# design.net
KiCad netlist of a schematic drawn in EAGLE
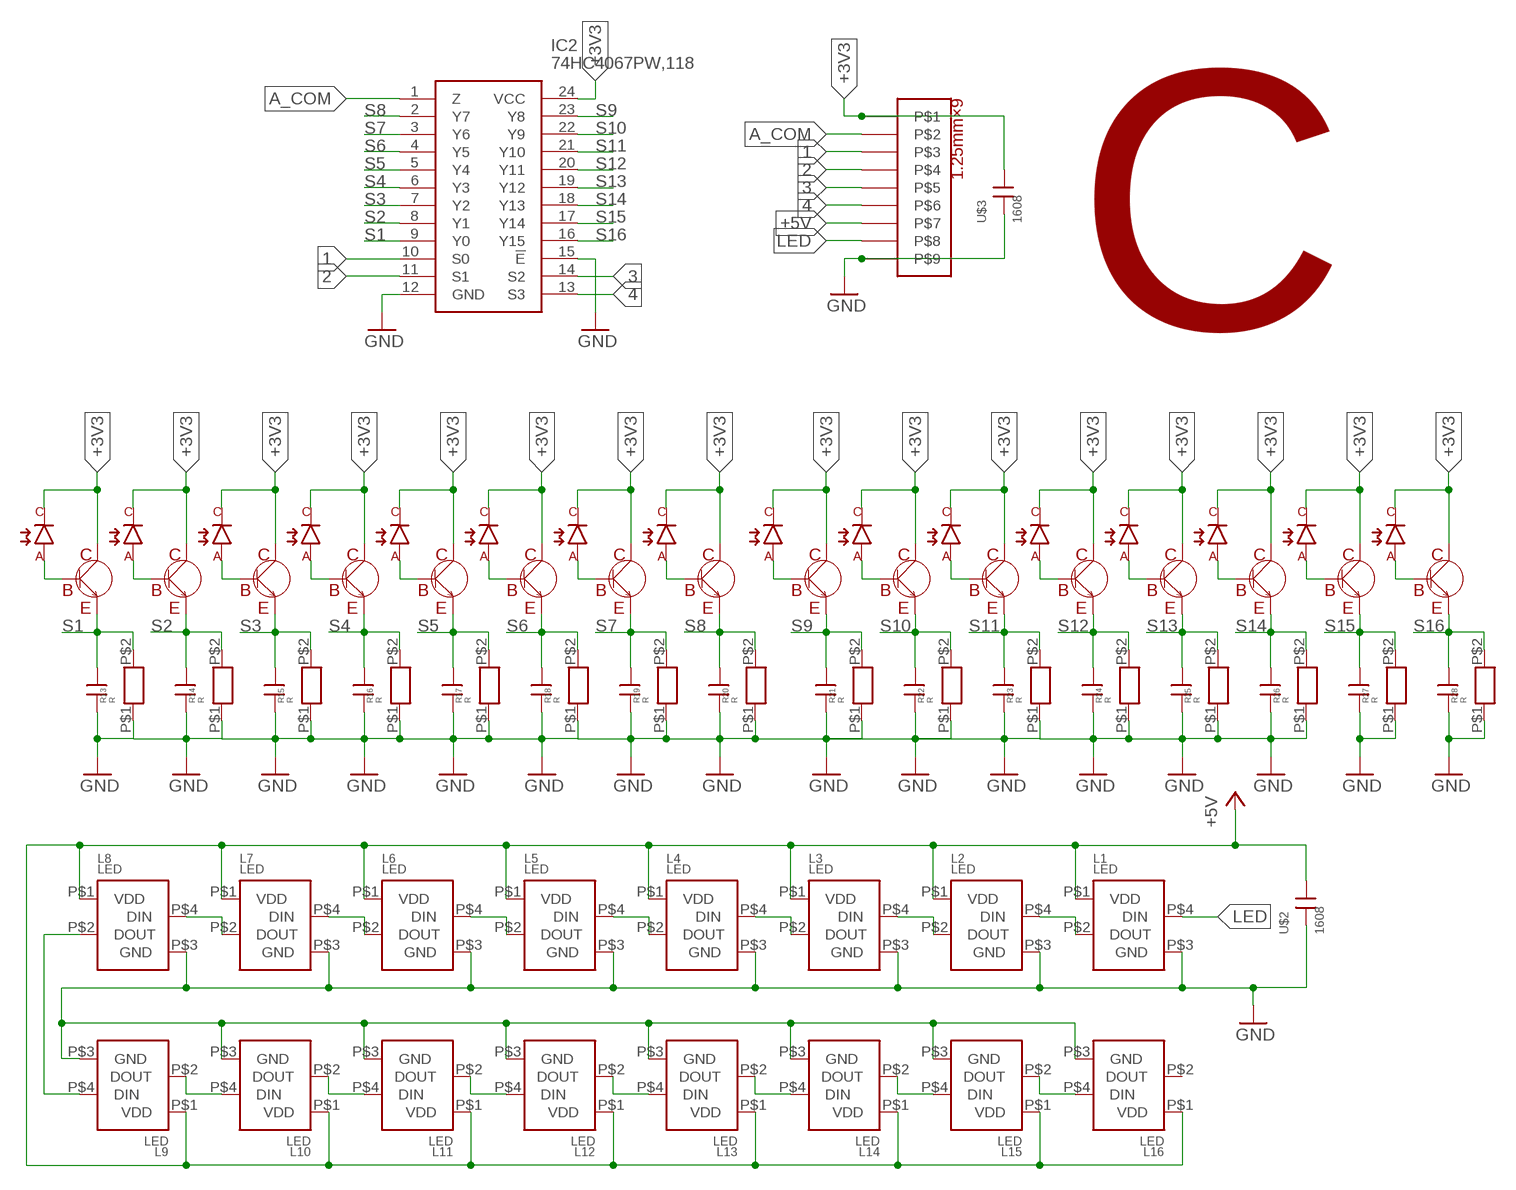
[diagram p0: schematic, sheet 1]

(export (version "E")
  (design (tool "Eeschema 10.0.6"))
  (components
    (comp (ref "C13")
      (value "1608")
      (footprint "eagle-import:CON")
      (libsource (lib "eagle-import") (part "1608"))
    )
    (comp (ref "C14")
      (value "1608")
      (footprint "eagle-import:CON")
      (libsource (lib "eagle-import") (part "1608"))
    )
    (comp (ref "C15")
      (value "1608")
      (footprint "eagle-import:CON")
      (libsource (lib "eagle-import") (part "1608"))
    )
    (comp (ref "C16")
      (value "1608")
      (footprint "eagle-import:CON")
      (libsource (lib "eagle-import") (part "1608"))
    )
    (comp (ref "C17")
      (value "1608")
      (footprint "eagle-import:CON")
      (libsource (lib "eagle-import") (part "1608"))
    )
    (comp (ref "C18")
      (value "1608")
      (footprint "eagle-import:CON")
      (libsource (lib "eagle-import") (part "1608"))
    )
    (comp (ref "C19")
      (value "1608")
      (footprint "eagle-import:CON")
      (libsource (lib "eagle-import") (part "1608"))
    )
    (comp (ref "C20")
      (value "1608")
      (footprint "eagle-import:CON")
      (libsource (lib "eagle-import") (part "1608"))
    )
    (comp (ref "C21")
      (value "1608")
      (footprint "eagle-import:CON")
      (libsource (lib "eagle-import") (part "1608"))
    )
    (comp (ref "C22")
      (value "1608")
      (footprint "eagle-import:CON")
      (libsource (lib "eagle-import") (part "1608"))
    )
    (comp (ref "C23")
      (value "1608")
      (footprint "eagle-import:CON")
      (libsource (lib "eagle-import") (part "1608"))
    )
    (comp (ref "C24")
      (value "1608")
      (footprint "eagle-import:CON")
      (libsource (lib "eagle-import") (part "1608"))
    )
    (comp (ref "C25")
      (value "1608")
      (footprint "eagle-import:CON")
      (libsource (lib "eagle-import") (part "1608"))
    )
    (comp (ref "C26")
      (value "1608")
      (footprint "eagle-import:CON")
      (libsource (lib "eagle-import") (part "1608"))
    )
    (comp (ref "C27")
      (value "1608")
      (footprint "eagle-import:CON")
      (libsource (lib "eagle-import") (part "1608"))
    )
    (comp (ref "C28")
      (value "1608")
      (footprint "eagle-import:CON")
      (libsource (lib "eagle-import") (part "1608"))
    )
    (comp (ref "IC2")
      (value "74HC4067PW,118")
      (footprint "eagle-import:SOP65P640X110-24N")
      (fields (field (name "MOUSER_PART_NUMBER") "771-74HC4067PW-T"))
      (libsource (lib "eagle-import") (part "74HC4067PW,118"))
    )
    (comp (ref "L1")
      (value "LED")
      (footprint "eagle-import:LED")
      (libsource (lib "eagle-import") (part "LED"))
    )
    (comp (ref "L2")
      (value "LED")
      (footprint "eagle-import:LED")
      (libsource (lib "eagle-import") (part "LED"))
    )
    (comp (ref "L3")
      (value "LED")
      (footprint "eagle-import:LED")
      (libsource (lib "eagle-import") (part "LED"))
    )
    (comp (ref "L4")
      (value "LED")
      (footprint "eagle-import:LED")
      (libsource (lib "eagle-import") (part "LED"))
    )
    (comp (ref "L5")
      (value "LED")
      (footprint "eagle-import:LED")
      (libsource (lib "eagle-import") (part "LED"))
    )
    (comp (ref "L6")
      (value "LED")
      (footprint "eagle-import:LED")
      (libsource (lib "eagle-import") (part "LED"))
    )
    (comp (ref "L7")
      (value "LED")
      (footprint "eagle-import:LED")
      (libsource (lib "eagle-import") (part "LED"))
    )
    (comp (ref "L8")
      (value "LED")
      (footprint "eagle-import:LED")
      (libsource (lib "eagle-import") (part "LED"))
    )
    (comp (ref "L9")
      (value "LED")
      (footprint "eagle-import:LED")
      (libsource (lib "eagle-import") (part "LED"))
    )
    (comp (ref "L10")
      (value "LED")
      (footprint "eagle-import:LED")
      (libsource (lib "eagle-import") (part "LED"))
    )
    (comp (ref "L11")
      (value "LED")
      (footprint "eagle-import:LED")
      (libsource (lib "eagle-import") (part "LED"))
    )
    (comp (ref "L12")
      (value "LED")
      (footprint "eagle-import:LED")
      (libsource (lib "eagle-import") (part "LED"))
    )
    (comp (ref "L13")
      (value "LED")
      (footprint "eagle-import:LED")
      (libsource (lib "eagle-import") (part "LED"))
    )
    (comp (ref "L14")
      (value "LED")
      (footprint "eagle-import:LED")
      (libsource (lib "eagle-import") (part "LED"))
    )
    (comp (ref "L15")
      (value "LED")
      (footprint "eagle-import:LED")
      (libsource (lib "eagle-import") (part "LED"))
    )
    (comp (ref "L16")
      (value "LED")
      (footprint "eagle-import:LED")
      (libsource (lib "eagle-import") (part "LED"))
    )
    (comp (ref "P1")
      (value "フォトダイオード")
      (footprint "eagle-import:フォトダイオード")
      (libsource (lib "eagle-import") (part "フォトダイオード"))
    )
    (comp (ref "P2")
      (value "フォトダイオード")
      (footprint "eagle-import:フォトダイオード")
      (libsource (lib "eagle-import") (part "フォトダイオード"))
    )
    (comp (ref "P3")
      (value "フォトダイオード")
      (footprint "eagle-import:フォトダイオード")
      (libsource (lib "eagle-import") (part "フォトダイオード"))
    )
    (comp (ref "P4")
      (value "フォトダイオード")
      (footprint "eagle-import:フォトダイオード")
      (libsource (lib "eagle-import") (part "フォトダイオード"))
    )
    (comp (ref "P5")
      (value "フォトダイオード")
      (footprint "eagle-import:フォトダイオード")
      (libsource (lib "eagle-import") (part "フォトダイオード"))
    )
    (comp (ref "P6")
      (value "フォトダイオード")
      (footprint "eagle-import:フォトダイオード")
      (libsource (lib "eagle-import") (part "フォトダイオード"))
    )
    (comp (ref "P7")
      (value "フォトダイオード")
      (footprint "eagle-import:フォトダイオード")
      (libsource (lib "eagle-import") (part "フォトダイオード"))
    )
    (comp (ref "P8")
      (value "フォトダイオード")
      (footprint "eagle-import:フォトダイオード")
      (libsource (lib "eagle-import") (part "フォトダイオード"))
    )
    (comp (ref "P9")
      (value "フォトダイオード")
      (footprint "eagle-import:フォトダイオード")
      (libsource (lib "eagle-import") (part "フォトダイオード"))
    )
    (comp (ref "P10")
      (value "フォトダイオード")
      (footprint "eagle-import:フォトダイオード")
      (libsource (lib "eagle-import") (part "フォトダイオード"))
    )
    (comp (ref "P11")
      (value "フォトダイオード")
      (footprint "eagle-import:フォトダイオード")
      (libsource (lib "eagle-import") (part "フォトダイオード"))
    )
    (comp (ref "P12")
      (value "フォトダイオード")
      (footprint "eagle-import:フォトダイオード")
      (libsource (lib "eagle-import") (part "フォトダイオード"))
    )
    (comp (ref "P13")
      (value "フォトダイオード")
      (footprint "eagle-import:フォトダイオード")
      (libsource (lib "eagle-import") (part "フォトダイオード"))
    )
    (comp (ref "P14")
      (value "フォトダイオード")
      (footprint "eagle-import:フォトダイオード")
      (libsource (lib "eagle-import") (part "フォトダイオード"))
    )
    (comp (ref "P15")
      (value "フォトダイオード")
      (footprint "eagle-import:フォトダイオード")
      (libsource (lib "eagle-import") (part "フォトダイオード"))
    )
    (comp (ref "P16")
      (value "フォトダイオード")
      (footprint "eagle-import:フォトダイオード")
      (libsource (lib "eagle-import") (part "フォトダイオード"))
    )
    (comp (ref "R13") (value "R") (footprint "eagle-import:1608") (libsource (lib "eagle-import") (part "R")))
    (comp (ref "R14") (value "R") (footprint "eagle-import:1608") (libsource (lib "eagle-import") (part "R")))
    (comp (ref "R15") (value "R") (footprint "eagle-import:1608") (libsource (lib "eagle-import") (part "R")))
    (comp (ref "R16") (value "R") (footprint "eagle-import:1608") (libsource (lib "eagle-import") (part "R")))
    (comp (ref "R17") (value "R") (footprint "eagle-import:1608") (libsource (lib "eagle-import") (part "R")))
    (comp (ref "R18") (value "R") (footprint "eagle-import:1608") (libsource (lib "eagle-import") (part "R")))
    (comp (ref "R19") (value "R") (footprint "eagle-import:1608") (libsource (lib "eagle-import") (part "R")))
    (comp (ref "R20") (value "R") (footprint "eagle-import:1608") (libsource (lib "eagle-import") (part "R")))
    (comp (ref "R21") (value "R") (footprint "eagle-import:1608") (libsource (lib "eagle-import") (part "R")))
    (comp (ref "R22") (value "R") (footprint "eagle-import:1608") (libsource (lib "eagle-import") (part "R")))
    (comp (ref "R23") (value "R") (footprint "eagle-import:1608") (libsource (lib "eagle-import") (part "R")))
    (comp (ref "R24") (value "R") (footprint "eagle-import:1608") (libsource (lib "eagle-import") (part "R")))
    (comp (ref "R25") (value "R") (footprint "eagle-import:1608") (libsource (lib "eagle-import") (part "R")))
    (comp (ref "R26") (value "R") (footprint "eagle-import:1608") (libsource (lib "eagle-import") (part "R")))
    (comp (ref "R27") (value "R") (footprint "eagle-import:1608") (libsource (lib "eagle-import") (part "R")))
    (comp (ref "R28") (value "R") (footprint "eagle-import:1608") (libsource (lib "eagle-import") (part "R")))
    (comp (ref "T1")
      (value "2CS2712")
      (footprint "eagle-import:TRANS_SSM3J325F,LF")
      (libsource (lib "eagle-import") (part "2CS2712"))
    )
    (comp (ref "T2")
      (value "2CS2712")
      (footprint "eagle-import:TRANS_SSM3J325F,LF")
      (libsource (lib "eagle-import") (part "2CS2712"))
    )
    (comp (ref "T3")
      (value "2CS2712")
      (footprint "eagle-import:TRANS_SSM3J325F,LF")
      (libsource (lib "eagle-import") (part "2CS2712"))
    )
    (comp (ref "T4")
      (value "2CS2712")
      (footprint "eagle-import:TRANS_SSM3J325F,LF")
      (libsource (lib "eagle-import") (part "2CS2712"))
    )
    (comp (ref "T5")
      (value "2CS2712")
      (footprint "eagle-import:TRANS_SSM3J325F,LF")
      (libsource (lib "eagle-import") (part "2CS2712"))
    )
    (comp (ref "T6")
      (value "2CS2712")
      (footprint "eagle-import:TRANS_SSM3J325F,LF")
      (libsource (lib "eagle-import") (part "2CS2712"))
    )
    (comp (ref "T7")
      (value "2CS2712")
      (footprint "eagle-import:TRANS_SSM3J325F,LF")
      (libsource (lib "eagle-import") (part "2CS2712"))
    )
    (comp (ref "T8")
      (value "2CS2712")
      (footprint "eagle-import:TRANS_SSM3J325F,LF")
      (libsource (lib "eagle-import") (part "2CS2712"))
    )
    (comp (ref "T9")
      (value "2CS2712")
      (footprint "eagle-import:TRANS_SSM3J325F,LF")
      (libsource (lib "eagle-import") (part "2CS2712"))
    )
    (comp (ref "T10")
      (value "2CS2712")
      (footprint "eagle-import:TRANS_SSM3J325F,LF")
      (libsource (lib "eagle-import") (part "2CS2712"))
    )
    (comp (ref "T11")
      (value "2CS2712")
      (footprint "eagle-import:TRANS_SSM3J325F,LF")
      (libsource (lib "eagle-import") (part "2CS2712"))
    )
    (comp (ref "T12")
      (value "2CS2712")
      (footprint "eagle-import:TRANS_SSM3J325F,LF")
      (libsource (lib "eagle-import") (part "2CS2712"))
    )
    (comp (ref "T13")
      (value "2CS2712")
      (footprint "eagle-import:TRANS_SSM3J325F,LF")
      (libsource (lib "eagle-import") (part "2CS2712"))
    )
    (comp (ref "T14")
      (value "2CS2712")
      (footprint "eagle-import:TRANS_SSM3J325F,LF")
      (libsource (lib "eagle-import") (part "2CS2712"))
    )
    (comp (ref "T15")
      (value "2CS2712")
      (footprint "eagle-import:TRANS_SSM3J325F,LF")
      (libsource (lib "eagle-import") (part "2CS2712"))
    )
    (comp (ref "T16")
      (value "2CS2712")
      (footprint "eagle-import:TRANS_SSM3J325F,LF")
      (libsource (lib "eagle-import") (part "2CS2712"))
    )
    (comp (ref "U$1")
      (value "1MMCON")
      (footprint "eagle-import:1MMCON")
      (libsource (lib "eagle-import") (part "1MMCON"))
    )
    (comp (ref "U$2")
      (value "1608")
      (footprint "eagle-import:CON")
      (libsource (lib "eagle-import") (part "1608"))
    )
    (comp (ref "U$3")
      (value "1608")
      (footprint "eagle-import:CON")
      (libsource (lib "eagle-import") (part "1608"))
    )
  )
  (nets
    (net (code "1") (name "+3V3") (class "Default")
      (node (ref "IC2") (pin "24") (pinfunction "VCC_24") (pintype "bidirectional"))
      (node (ref "P1") (pin "C") (pinfunction "C_C") (pintype "bidirectional"))
      (node (ref "P10") (pin "C") (pinfunction "C_C") (pintype "bidirectional"))
      (node (ref "P11") (pin "C") (pinfunction "C_C") (pintype "bidirectional"))
      (node (ref "P12") (pin "C") (pinfunction "C_C") (pintype "bidirectional"))
      (node (ref "P13") (pin "C") (pinfunction "C_C") (pintype "bidirectional"))
      (node (ref "P14") (pin "C") (pinfunction "C_C") (pintype "bidirectional"))
      (node (ref "P15") (pin "C") (pinfunction "C_C") (pintype "bidirectional"))
      (node (ref "P16") (pin "C") (pinfunction "C_C") (pintype "bidirectional"))
      (node (ref "P2") (pin "C") (pinfunction "C_C") (pintype "bidirectional"))
      (node (ref "P3") (pin "C") (pinfunction "C_C") (pintype "bidirectional"))
      (node (ref "P4") (pin "C") (pinfunction "C_C") (pintype "bidirectional"))
      (node (ref "P5") (pin "C") (pinfunction "C_C") (pintype "bidirectional"))
      (node (ref "P6") (pin "C") (pinfunction "C_C") (pintype "bidirectional"))
      (node (ref "P7") (pin "C") (pinfunction "C_C") (pintype "bidirectional"))
      (node (ref "P8") (pin "C") (pinfunction "C_C") (pintype "bidirectional"))
      (node (ref "P9") (pin "C") (pinfunction "C_C") (pintype "bidirectional"))
      (node (ref "T1") (pin "C") (pinfunction "C_C") (pintype "bidirectional"))
      (node (ref "T10") (pin "C") (pinfunction "C_C") (pintype "bidirectional"))
      (node (ref "T11") (pin "C") (pinfunction "C_C") (pintype "bidirectional"))
      (node (ref "T12") (pin "C") (pinfunction "C_C") (pintype "bidirectional"))
      (node (ref "T13") (pin "C") (pinfunction "C_C") (pintype "bidirectional"))
      (node (ref "T14") (pin "C") (pinfunction "C_C") (pintype "bidirectional"))
      (node (ref "T15") (pin "C") (pinfunction "C_C") (pintype "bidirectional"))
      (node (ref "T16") (pin "C") (pinfunction "C_C") (pintype "bidirectional"))
      (node (ref "T2") (pin "C") (pinfunction "C_C") (pintype "bidirectional"))
      (node (ref "T3") (pin "C") (pinfunction "C_C") (pintype "bidirectional"))
      (node (ref "T4") (pin "C") (pinfunction "C_C") (pintype "bidirectional"))
      (node (ref "T5") (pin "C") (pinfunction "C_C") (pintype "bidirectional"))
      (node (ref "T6") (pin "C") (pinfunction "C_C") (pintype "bidirectional"))
      (node (ref "T7") (pin "C") (pinfunction "C_C") (pintype "bidirectional"))
      (node (ref "T8") (pin "C") (pinfunction "C_C") (pintype "bidirectional"))
      (node (ref "T9") (pin "C") (pinfunction "C_C") (pintype "bidirectional"))
      (node (ref "U$1") (pin "P$1") (pinfunction "P$1_P$1") (pintype "bidirectional"))
      (node (ref "U$3") (pin "P$1") (pinfunction "1_P$1") (pintype "bidirectional"))
    )
    (net (code "2") (name "+5V") (class "Default")
      (node (ref "L1") (pin "P$1") (pinfunction "VDD_P$1") (pintype "bidirectional"))
      (node (ref "L10") (pin "P$1") (pinfunction "VDD_P$1") (pintype "bidirectional"))
      (node (ref "L11") (pin "P$1") (pinfunction "VDD_P$1") (pintype "bidirectional"))
      (node (ref "L12") (pin "P$1") (pinfunction "VDD_P$1") (pintype "bidirectional"))
      (node (ref "L13") (pin "P$1") (pinfunction "VDD_P$1") (pintype "bidirectional"))
      (node (ref "L14") (pin "P$1") (pinfunction "VDD_P$1") (pintype "bidirectional"))
      (node (ref "L15") (pin "P$1") (pinfunction "VDD_P$1") (pintype "bidirectional"))
      (node (ref "L16") (pin "P$1") (pinfunction "VDD_P$1") (pintype "bidirectional"))
      (node (ref "L2") (pin "P$1") (pinfunction "VDD_P$1") (pintype "bidirectional"))
      (node (ref "L3") (pin "P$1") (pinfunction "VDD_P$1") (pintype "bidirectional"))
      (node (ref "L4") (pin "P$1") (pinfunction "VDD_P$1") (pintype "bidirectional"))
      (node (ref "L5") (pin "P$1") (pinfunction "VDD_P$1") (pintype "bidirectional"))
      (node (ref "L6") (pin "P$1") (pinfunction "VDD_P$1") (pintype "bidirectional"))
      (node (ref "L7") (pin "P$1") (pinfunction "VDD_P$1") (pintype "bidirectional"))
      (node (ref "L8") (pin "P$1") (pinfunction "VDD_P$1") (pintype "bidirectional"))
      (node (ref "L9") (pin "P$1") (pinfunction "VDD_P$1") (pintype "bidirectional"))
      (node (ref "U$1") (pin "P$7") (pinfunction "P$7_P$7") (pintype "bidirectional"))
      (node (ref "U$2") (pin "P$1") (pinfunction "1_P$1") (pintype "bidirectional"))
    )
    (net (code "3") (name "/S1") (class "Default")
      (node (ref "C13") (pin "P$1") (pinfunction "1_P$1") (pintype "bidirectional"))
      (node (ref "IC2") (pin "9") (pinfunction "Y0_9") (pintype "bidirectional"))
      (node (ref "R13") (pin "P$2") (pinfunction "P$2_P$2") (pintype "bidirectional"))
      (node (ref "T1") (pin "E") (pinfunction "E_E") (pintype "bidirectional"))
    )
    (net (code "4") (name "/S2") (class "Default")
      (node (ref "C14") (pin "P$1") (pinfunction "1_P$1") (pintype "bidirectional"))
      (node (ref "IC2") (pin "8") (pinfunction "Y1_8") (pintype "bidirectional"))
      (node (ref "R14") (pin "P$2") (pinfunction "P$2_P$2") (pintype "bidirectional"))
      (node (ref "T2") (pin "E") (pinfunction "E_E") (pintype "bidirectional"))
    )
    (net (code "5") (name "/S3") (class "Default")
      (node (ref "C15") (pin "P$1") (pinfunction "1_P$1") (pintype "bidirectional"))
      (node (ref "IC2") (pin "7") (pinfunction "Y2_7") (pintype "bidirectional"))
      (node (ref "R15") (pin "P$2") (pinfunction "P$2_P$2") (pintype "bidirectional"))
      (node (ref "T3") (pin "E") (pinfunction "E_E") (pintype "bidirectional"))
    )
    (net (code "6") (name "/S4") (class "Default")
      (node (ref "C16") (pin "P$1") (pinfunction "1_P$1") (pintype "bidirectional"))
      (node (ref "IC2") (pin "6") (pinfunction "Y3_6") (pintype "bidirectional"))
      (node (ref "R16") (pin "P$2") (pinfunction "P$2_P$2") (pintype "bidirectional"))
      (node (ref "T4") (pin "E") (pinfunction "E_E") (pintype "bidirectional"))
    )
    (net (code "7") (name "/S5") (class "Default")
      (node (ref "C17") (pin "P$1") (pinfunction "1_P$1") (pintype "bidirectional"))
      (node (ref "IC2") (pin "5") (pinfunction "Y4_5") (pintype "bidirectional"))
      (node (ref "R17") (pin "P$2") (pinfunction "P$2_P$2") (pintype "bidirectional"))
      (node (ref "T5") (pin "E") (pinfunction "E_E") (pintype "bidirectional"))
    )
    (net (code "8") (name "/S6") (class "Default")
      (node (ref "C18") (pin "P$1") (pinfunction "1_P$1") (pintype "bidirectional"))
      (node (ref "IC2") (pin "4") (pinfunction "Y5_4") (pintype "bidirectional"))
      (node (ref "R18") (pin "P$2") (pinfunction "P$2_P$2") (pintype "bidirectional"))
      (node (ref "T6") (pin "E") (pinfunction "E_E") (pintype "bidirectional"))
    )
    (net (code "9") (name "/S7") (class "Default")
      (node (ref "C19") (pin "P$1") (pinfunction "1_P$1") (pintype "bidirectional"))
      (node (ref "IC2") (pin "3") (pinfunction "Y6_3") (pintype "bidirectional"))
      (node (ref "R19") (pin "P$2") (pinfunction "P$2_P$2") (pintype "bidirectional"))
      (node (ref "T7") (pin "E") (pinfunction "E_E") (pintype "bidirectional"))
    )
    (net (code "10") (name "/S8") (class "Default")
      (node (ref "C20") (pin "P$1") (pinfunction "1_P$1") (pintype "bidirectional"))
      (node (ref "IC2") (pin "2") (pinfunction "Y7_2") (pintype "bidirectional"))
      (node (ref "R20") (pin "P$2") (pinfunction "P$2_P$2") (pintype "bidirectional"))
      (node (ref "T8") (pin "E") (pinfunction "E_E") (pintype "bidirectional"))
    )
    (net (code "11") (name "/S9") (class "Default")
      (node (ref "C21") (pin "P$1") (pinfunction "1_P$1") (pintype "bidirectional"))
      (node (ref "IC2") (pin "23") (pinfunction "Y8_23") (pintype "bidirectional"))
      (node (ref "R21") (pin "P$2") (pinfunction "P$2_P$2") (pintype "bidirectional"))
      (node (ref "T9") (pin "E") (pinfunction "E_E") (pintype "bidirectional"))
    )
    (net (code "12") (name "/S10") (class "Default")
      (node (ref "C22") (pin "P$1") (pinfunction "1_P$1") (pintype "bidirectional"))
      (node (ref "IC2") (pin "22") (pinfunction "Y9_22") (pintype "bidirectional"))
      (node (ref "R22") (pin "P$2") (pinfunction "P$2_P$2") (pintype "bidirectional"))
      (node (ref "T10") (pin "E") (pinfunction "E_E") (pintype "bidirectional"))
    )
    (net (code "13") (name "/S11") (class "Default")
      (node (ref "C23") (pin "P$1") (pinfunction "1_P$1") (pintype "bidirectional"))
      (node (ref "IC2") (pin "21") (pinfunction "Y10_21") (pintype "bidirectional"))
      (node (ref "R23") (pin "P$2") (pinfunction "P$2_P$2") (pintype "bidirectional"))
      (node (ref "T11") (pin "E") (pinfunction "E_E") (pintype "bidirectional"))
    )
    (net (code "14") (name "/S12") (class "Default")
      (node (ref "C24") (pin "P$1") (pinfunction "1_P$1") (pintype "bidirectional"))
      (node (ref "IC2") (pin "20") (pinfunction "Y11_20") (pintype "bidirectional"))
      (node (ref "R24") (pin "P$2") (pinfunction "P$2_P$2") (pintype "bidirectional"))
      (node (ref "T12") (pin "E") (pinfunction "E_E") (pintype "bidirectional"))
    )
    (net (code "15") (name "/S13") (class "Default")
      (node (ref "C25") (pin "P$1") (pinfunction "1_P$1") (pintype "bidirectional"))
      (node (ref "IC2") (pin "19") (pinfunction "Y12_19") (pintype "bidirectional"))
      (node (ref "R25") (pin "P$2") (pinfunction "P$2_P$2") (pintype "bidirectional"))
      (node (ref "T13") (pin "E") (pinfunction "E_E") (pintype "bidirectional"))
    )
    (net (code "16") (name "/S14") (class "Default")
      (node (ref "C26") (pin "P$1") (pinfunction "1_P$1") (pintype "bidirectional"))
      (node (ref "IC2") (pin "18") (pinfunction "Y13_18") (pintype "bidirectional"))
      (node (ref "R26") (pin "P$2") (pinfunction "P$2_P$2") (pintype "bidirectional"))
      (node (ref "T14") (pin "E") (pinfunction "E_E") (pintype "bidirectional"))
    )
    (net (code "17") (name "/S15") (class "Default")
      (node (ref "C27") (pin "P$1") (pinfunction "1_P$1") (pintype "bidirectional"))
      (node (ref "IC2") (pin "17") (pinfunction "Y14_17") (pintype "bidirectional"))
      (node (ref "R27") (pin "P$2") (pinfunction "P$2_P$2") (pintype "bidirectional"))
      (node (ref "T15") (pin "E") (pinfunction "E_E") (pintype "bidirectional"))
    )
    (net (code "18") (name "/S16") (class "Default")
      (node (ref "C28") (pin "P$1") (pinfunction "1_P$1") (pintype "bidirectional"))
      (node (ref "IC2") (pin "16") (pinfunction "Y15_16") (pintype "bidirectional"))
      (node (ref "R28") (pin "P$2") (pinfunction "P$2_P$2") (pintype "bidirectional"))
      (node (ref "T16") (pin "E") (pinfunction "E_E") (pintype "bidirectional"))
    )
    (net (code "19") (name "1") (class "Default")
      (node (ref "IC2") (pin "10") (pinfunction "S0_10") (pintype "bidirectional"))
      (node (ref "U$1") (pin "P$3") (pinfunction "P$3_P$3") (pintype "bidirectional"))
    )
    (net (code "20") (name "2") (class "Default")
      (node (ref "IC2") (pin "11") (pinfunction "S1_11") (pintype "bidirectional"))
      (node (ref "U$1") (pin "P$4") (pinfunction "P$4_P$4") (pintype "bidirectional"))
    )
    (net (code "21") (name "3") (class "Default")
      (node (ref "IC2") (pin "14") (pinfunction "S2_14") (pintype "bidirectional"))
      (node (ref "U$1") (pin "P$5") (pinfunction "P$5_P$5") (pintype "bidirectional"))
    )
    (net (code "22") (name "4") (class "Default")
      (node (ref "IC2") (pin "13") (pinfunction "S3_13") (pintype "bidirectional"))
      (node (ref "U$1") (pin "P$6") (pinfunction "P$6_P$6") (pintype "bidirectional"))
    )
    (net (code "23") (name "A_COM") (class "Default")
      (node (ref "IC2") (pin "1") (pinfunction "Z_1") (pintype "bidirectional"))
      (node (ref "U$1") (pin "P$2") (pinfunction "P$2_P$2") (pintype "bidirectional"))
    )
    (net (code "24") (name "GND") (class "Default")
      (node (ref "C13") (pin "P$2") (pinfunction "2_P$2") (pintype "bidirectional"))
      (node (ref "C14") (pin "P$2") (pinfunction "2_P$2") (pintype "bidirectional"))
      (node (ref "C15") (pin "P$2") (pinfunction "2_P$2") (pintype "bidirectional"))
      (node (ref "C16") (pin "P$2") (pinfunction "2_P$2") (pintype "bidirectional"))
      (node (ref "C17") (pin "P$2") (pinfunction "2_P$2") (pintype "bidirectional"))
      (node (ref "C18") (pin "P$2") (pinfunction "2_P$2") (pintype "bidirectional"))
      (node (ref "C19") (pin "P$2") (pinfunction "2_P$2") (pintype "bidirectional"))
      (node (ref "C20") (pin "P$2") (pinfunction "2_P$2") (pintype "bidirectional"))
      (node (ref "C21") (pin "P$2") (pinfunction "2_P$2") (pintype "bidirectional"))
      (node (ref "C22") (pin "P$2") (pinfunction "2_P$2") (pintype "bidirectional"))
      (node (ref "C23") (pin "P$2") (pinfunction "2_P$2") (pintype "bidirectional"))
      (node (ref "C24") (pin "P$2") (pinfunction "2_P$2") (pintype "bidirectional"))
      (node (ref "C25") (pin "P$2") (pinfunction "2_P$2") (pintype "bidirectional"))
      (node (ref "C26") (pin "P$2") (pinfunction "2_P$2") (pintype "bidirectional"))
      (node (ref "C27") (pin "P$2") (pinfunction "2_P$2") (pintype "bidirectional"))
      (node (ref "C28") (pin "P$2") (pinfunction "2_P$2") (pintype "bidirectional"))
      (node (ref "IC2") (pin "12") (pinfunction "GND_12") (pintype "bidirectional"))
      (node (ref "IC2") (pin "15") (pinfunction "~{E}_15") (pintype "bidirectional"))
      (node (ref "L1") (pin "P$3") (pinfunction "GND_P$3") (pintype "bidirectional"))
      (node (ref "L10") (pin "P$3") (pinfunction "GND_P$3") (pintype "bidirectional"))
      (node (ref "L11") (pin "P$3") (pinfunction "GND_P$3") (pintype "bidirectional"))
      (node (ref "L12") (pin "P$3") (pinfunction "GND_P$3") (pintype "bidirectional"))
      (node (ref "L13") (pin "P$3") (pinfunction "GND_P$3") (pintype "bidirectional"))
      (node (ref "L14") (pin "P$3") (pinfunction "GND_P$3") (pintype "bidirectional"))
      (node (ref "L15") (pin "P$3") (pinfunction "GND_P$3") (pintype "bidirectional"))
      (node (ref "L16") (pin "P$3") (pinfunction "GND_P$3") (pintype "bidirectional"))
      (node (ref "L2") (pin "P$3") (pinfunction "GND_P$3") (pintype "bidirectional"))
      (node (ref "L3") (pin "P$3") (pinfunction "GND_P$3") (pintype "bidirectional"))
      (node (ref "L4") (pin "P$3") (pinfunction "GND_P$3") (pintype "bidirectional"))
      (node (ref "L5") (pin "P$3") (pinfunction "GND_P$3") (pintype "bidirectional"))
      (node (ref "L6") (pin "P$3") (pinfunction "GND_P$3") (pintype "bidirectional"))
      (node (ref "L7") (pin "P$3") (pinfunction "GND_P$3") (pintype "bidirectional"))
      (node (ref "L8") (pin "P$3") (pinfunction "GND_P$3") (pintype "bidirectional"))
      (node (ref "L9") (pin "P$3") (pinfunction "GND_P$3") (pintype "bidirectional"))
      (node (ref "R13") (pin "P$1") (pinfunction "P$1_P$1") (pintype "bidirectional"))
      (node (ref "R14") (pin "P$1") (pinfunction "P$1_P$1") (pintype "bidirectional"))
      (node (ref "R15") (pin "P$1") (pinfunction "P$1_P$1") (pintype "bidirectional"))
      (node (ref "R16") (pin "P$1") (pinfunction "P$1_P$1") (pintype "bidirectional"))
      (node (ref "R17") (pin "P$1") (pinfunction "P$1_P$1") (pintype "bidirectional"))
      (node (ref "R18") (pin "P$1") (pinfunction "P$1_P$1") (pintype "bidirectional"))
      (node (ref "R19") (pin "P$1") (pinfunction "P$1_P$1") (pintype "bidirectional"))
      (node (ref "R20") (pin "P$1") (pinfunction "P$1_P$1") (pintype "bidirectional"))
      (node (ref "R21") (pin "P$1") (pinfunction "P$1_P$1") (pintype "bidirectional"))
      (node (ref "R22") (pin "P$1") (pinfunction "P$1_P$1") (pintype "bidirectional"))
      (node (ref "R23") (pin "P$1") (pinfunction "P$1_P$1") (pintype "bidirectional"))
      (node (ref "R24") (pin "P$1") (pinfunction "P$1_P$1") (pintype "bidirectional"))
      (node (ref "R25") (pin "P$1") (pinfunction "P$1_P$1") (pintype "bidirectional"))
      (node (ref "R26") (pin "P$1") (pinfunction "P$1_P$1") (pintype "bidirectional"))
      (node (ref "R27") (pin "P$1") (pinfunction "P$1_P$1") (pintype "bidirectional"))
      (node (ref "R28") (pin "P$1") (pinfunction "P$1_P$1") (pintype "bidirectional"))
      (node (ref "U$1") (pin "P$9") (pinfunction "P$9_P$9") (pintype "bidirectional"))
      (node (ref "U$2") (pin "P$2") (pinfunction "2_P$2") (pintype "bidirectional"))
      (node (ref "U$3") (pin "P$2") (pinfunction "2_P$2") (pintype "bidirectional"))
    )
    (net (code "25") (name "LED") (class "Default")
      (node (ref "L1") (pin "P$4") (pinfunction "DIN_P$4") (pintype "bidirectional"))
      (node (ref "U$1") (pin "P$8") (pinfunction "P$8_P$8") (pintype "bidirectional"))
    )
    (net (code "26") (name "Net-(L1-DOUT)") (class "Default")
      (node (ref "L1") (pin "P$2") (pinfunction "DOUT_P$2") (pintype "bidirectional"))
      (node (ref "L2") (pin "P$4") (pinfunction "DIN_P$4") (pintype "bidirectional"))
    )
    (net (code "27") (name "Net-(L2-DOUT)") (class "Default")
      (node (ref "L2") (pin "P$2") (pinfunction "DOUT_P$2") (pintype "bidirectional"))
      (node (ref "L3") (pin "P$4") (pinfunction "DIN_P$4") (pintype "bidirectional"))
    )
    (net (code "28") (name "Net-(L3-DOUT)") (class "Default")
      (node (ref "L3") (pin "P$2") (pinfunction "DOUT_P$2") (pintype "bidirectional"))
      (node (ref "L4") (pin "P$4") (pinfunction "DIN_P$4") (pintype "bidirectional"))
    )
    (net (code "29") (name "Net-(L4-DOUT)") (class "Default")
      (node (ref "L4") (pin "P$2") (pinfunction "DOUT_P$2") (pintype "bidirectional"))
      (node (ref "L5") (pin "P$4") (pinfunction "DIN_P$4") (pintype "bidirectional"))
    )
    (net (code "30") (name "Net-(L5-DOUT)") (class "Default")
      (node (ref "L5") (pin "P$2") (pinfunction "DOUT_P$2") (pintype "bidirectional"))
      (node (ref "L6") (pin "P$4") (pinfunction "DIN_P$4") (pintype "bidirectional"))
    )
    (net (code "31") (name "Net-(L6-DOUT)") (class "Default")
      (node (ref "L6") (pin "P$2") (pinfunction "DOUT_P$2") (pintype "bidirectional"))
      (node (ref "L7") (pin "P$4") (pinfunction "DIN_P$4") (pintype "bidirectional"))
    )
    (net (code "32") (name "Net-(L7-DOUT)") (class "Default")
      (node (ref "L7") (pin "P$2") (pinfunction "DOUT_P$2") (pintype "bidirectional"))
      (node (ref "L8") (pin "P$4") (pinfunction "DIN_P$4") (pintype "bidirectional"))
    )
    (net (code "33") (name "Net-(L8-DOUT)") (class "Default")
      (node (ref "L8") (pin "P$2") (pinfunction "DOUT_P$2") (pintype "bidirectional"))
      (node (ref "L9") (pin "P$4") (pinfunction "DIN_P$4") (pintype "bidirectional"))
    )
    (net (code "34") (name "Net-(L10-DIN)") (class "Default")
      (node (ref "L10") (pin "P$4") (pinfunction "DIN_P$4") (pintype "bidirectional"))
      (node (ref "L9") (pin "P$2") (pinfunction "DOUT_P$2") (pintype "bidirectional"))
    )
    (net (code "35") (name "Net-(L10-DOUT)") (class "Default")
      (node (ref "L10") (pin "P$2") (pinfunction "DOUT_P$2") (pintype "bidirectional"))
      (node (ref "L11") (pin "P$4") (pinfunction "DIN_P$4") (pintype "bidirectional"))
    )
    (net (code "36") (name "Net-(L11-DOUT)") (class "Default")
      (node (ref "L11") (pin "P$2") (pinfunction "DOUT_P$2") (pintype "bidirectional"))
      (node (ref "L12") (pin "P$4") (pinfunction "DIN_P$4") (pintype "bidirectional"))
    )
    (net (code "37") (name "Net-(L12-DOUT)") (class "Default")
      (node (ref "L12") (pin "P$2") (pinfunction "DOUT_P$2") (pintype "bidirectional"))
      (node (ref "L13") (pin "P$4") (pinfunction "DIN_P$4") (pintype "bidirectional"))
    )
    (net (code "38") (name "Net-(L13-DOUT)") (class "Default")
      (node (ref "L13") (pin "P$2") (pinfunction "DOUT_P$2") (pintype "bidirectional"))
      (node (ref "L14") (pin "P$4") (pinfunction "DIN_P$4") (pintype "bidirectional"))
    )
    (net (code "39") (name "Net-(L14-DOUT)") (class "Default")
      (node (ref "L14") (pin "P$2") (pinfunction "DOUT_P$2") (pintype "bidirectional"))
      (node (ref "L15") (pin "P$4") (pinfunction "DIN_P$4") (pintype "bidirectional"))
    )
    (net (code "40") (name "Net-(L15-DOUT)") (class "Default")
      (node (ref "L15") (pin "P$2") (pinfunction "DOUT_P$2") (pintype "bidirectional"))
      (node (ref "L16") (pin "P$4") (pinfunction "DIN_P$4") (pintype "bidirectional"))
    )
    (net (code "41") (name "Net-(P1-PadA)") (class "Default")
      (node (ref "P1") (pin "A") (pinfunction "A_A") (pintype "bidirectional"))
      (node (ref "T1") (pin "B") (pinfunction "B_B") (pintype "bidirectional"))
    )
    (net (code "42") (name "Net-(P2-PadA)") (class "Default")
      (node (ref "P2") (pin "A") (pinfunction "A_A") (pintype "bidirectional"))
      (node (ref "T2") (pin "B") (pinfunction "B_B") (pintype "bidirectional"))
    )
    (net (code "43") (name "Net-(P3-PadA)") (class "Default")
      (node (ref "P3") (pin "A") (pinfunction "A_A") (pintype "bidirectional"))
      (node (ref "T3") (pin "B") (pinfunction "B_B") (pintype "bidirectional"))
    )
    (net (code "44") (name "Net-(P4-PadA)") (class "Default")
      (node (ref "P4") (pin "A") (pinfunction "A_A") (pintype "bidirectional"))
      (node (ref "T4") (pin "B") (pinfunction "B_B") (pintype "bidirectional"))
    )
    (net (code "45") (name "Net-(P5-PadA)") (class "Default")
      (node (ref "P5") (pin "A") (pinfunction "A_A") (pintype "bidirectional"))
      (node (ref "T5") (pin "B") (pinfunction "B_B") (pintype "bidirectional"))
    )
    (net (code "46") (name "Net-(P6-PadA)") (class "Default")
      (node (ref "P6") (pin "A") (pinfunction "A_A") (pintype "bidirectional"))
      (node (ref "T6") (pin "B") (pinfunction "B_B") (pintype "bidirectional"))
    )
    (net (code "47") (name "Net-(P7-PadA)") (class "Default")
      (node (ref "P7") (pin "A") (pinfunction "A_A") (pintype "bidirectional"))
      (node (ref "T7") (pin "B") (pinfunction "B_B") (pintype "bidirectional"))
    )
    (net (code "48") (name "Net-(P8-PadA)") (class "Default")
      (node (ref "P8") (pin "A") (pinfunction "A_A") (pintype "bidirectional"))
      (node (ref "T8") (pin "B") (pinfunction "B_B") (pintype "bidirectional"))
    )
    (net (code "49") (name "Net-(P9-PadA)") (class "Default")
      (node (ref "P9") (pin "A") (pinfunction "A_A") (pintype "bidirectional"))
      (node (ref "T9") (pin "B") (pinfunction "B_B") (pintype "bidirectional"))
    )
    (net (code "50") (name "Net-(P10-PadA)") (class "Default")
      (node (ref "P10") (pin "A") (pinfunction "A_A") (pintype "bidirectional"))
      (node (ref "T10") (pin "B") (pinfunction "B_B") (pintype "bidirectional"))
    )
    (net (code "51") (name "Net-(P11-PadA)") (class "Default")
      (node (ref "P11") (pin "A") (pinfunction "A_A") (pintype "bidirectional"))
      (node (ref "T11") (pin "B") (pinfunction "B_B") (pintype "bidirectional"))
    )
    (net (code "52") (name "Net-(P12-PadA)") (class "Default")
      (node (ref "P12") (pin "A") (pinfunction "A_A") (pintype "bidirectional"))
      (node (ref "T12") (pin "B") (pinfunction "B_B") (pintype "bidirectional"))
    )
    (net (code "53") (name "Net-(P13-PadA)") (class "Default")
      (node (ref "P13") (pin "A") (pinfunction "A_A") (pintype "bidirectional"))
      (node (ref "T13") (pin "B") (pinfunction "B_B") (pintype "bidirectional"))
    )
    (net (code "54") (name "Net-(P14-PadA)") (class "Default")
      (node (ref "P14") (pin "A") (pinfunction "A_A") (pintype "bidirectional"))
      (node (ref "T14") (pin "B") (pinfunction "B_B") (pintype "bidirectional"))
    )
    (net (code "55") (name "Net-(P15-PadA)") (class "Default")
      (node (ref "P15") (pin "A") (pinfunction "A_A") (pintype "bidirectional"))
      (node (ref "T15") (pin "B") (pinfunction "B_B") (pintype "bidirectional"))
    )
    (net (code "56") (name "Net-(P16-PadA)") (class "Default")
      (node (ref "P16") (pin "A") (pinfunction "A_A") (pintype "bidirectional"))
      (node (ref "T16") (pin "B") (pinfunction "B_B") (pintype "bidirectional"))
    )
    (net (code "57") (name "unconnected-(L16-DOUT-PadP$2)") (class "Default")
      (node (ref "L16") (pin "P$2") (pinfunction "DOUT_P$2") (pintype "bidirectional"))
    )
  )
)
